# Limit_Switch_RGB_Vertical_v1_0.net
KiCad netlist of a schematic drawn in Altium Designer
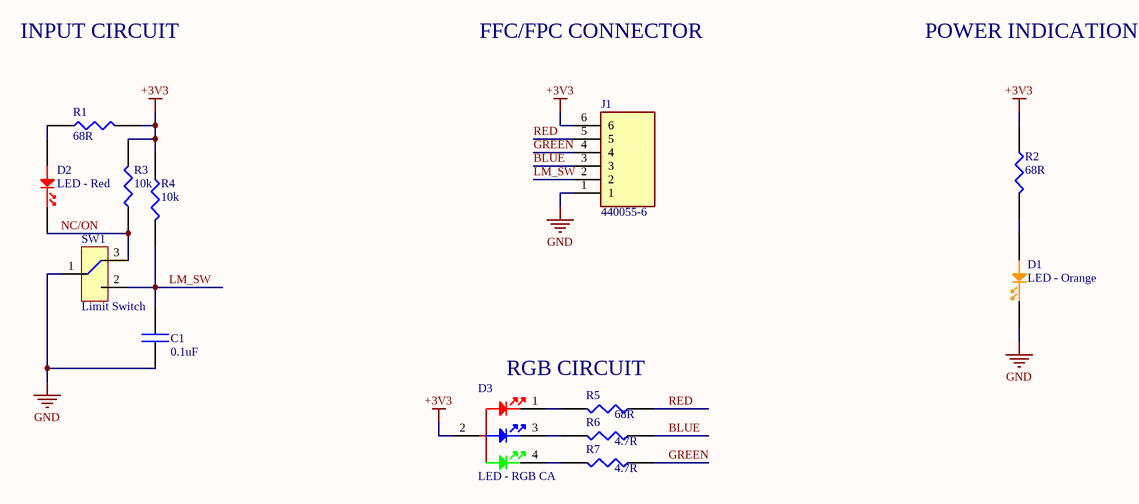
[diagram p0: Limit_Switch_RGB_Vertical_v1.0.SchDoc]

(export (version "E")
  (design (tool "Eeschema 10.0.6"))
  (components
    (comp (ref "C1")
      (value "0.1uF")
      (footprint "0.1uF 0603")
      (description "CAP CER 0.1UF 16V X7R 0603")
      (fields
        (field (name "MANUFACTURER") "KEMET")
        (field (name "MANUFACTURER PART NUMBER") "C0603C104M4RACTU")
      )
      (libsource (lib "Limit_Switch_RGB") (part "C0603C104M4RACTU"))
    )
    (comp (ref "D1")
      (value "LED - Orange")
      (footprint "LED0603-Orange")
      (description "LED ORANGE CLEAR SMD")
      (fields
        (field (name "MANUFACTURER") "Vishay Lite-On")
        (field (name "MANUFACTURER PART NUMBER") "LTST-C191KFKT")
      )
      (libsource (lib "Limit_Switch_RGB") (part "LTST-C191KFKT"))
    )
    (comp (ref "D2")
      (value "LED - Red")
      (footprint "LED RED 0603")
      (description "On a Reel of 5000, 2.4 V Red LED 1608 (0603) SMD, Lite-On LTST-C191KRKT")
      (fields
        (field (name "MANUFACTURER") "Vishay Lite-On")
        (field (name "MANUFACTURER PART NUMBER") "LTST-C191KRKT")
      )
      (libsource (lib "Limit_Switch_RGB") (part "LTST-C191KRKT"))
    )
    (comp (ref "D3")
      (value "LED - RGB CA")
      (footprint "LED RGB CA 3528")
      (description "Multicolor LED Red/Green/Blue 624nm/535nm/475nm 50mA/25mA/25mA 4-Pin SMD T/R")
      (fields
        (field (name "MANUFACTURER") "Cree")
        (field (name "MANUFACTURER PART NUMBER") "CLV1A-FKB-CK1VW1DE1BB7C3C3")
      )
      (libsource (lib "Limit_Switch_RGB") (part "CLV1A-FKB-CK1VW1DE1BB7C3C3"))
    )
    (comp (ref "J1")
      (value "440055-6")
      (footprint "TE_440055-6")
      (fields (field (name "MF") "{'manufacturer': 'TE Connectivity'}"))
      (libsource (lib "440055-6") (part "440055-6"))
    )
    (comp (ref "R1")
      (value "68R")
      (footprint "68R 0603")
      (description "CRGP 0603 68R 1%")
      (fields
        (field (name "MANUFACTURER") "TE Connectivity")
        (field (name "MANUFACTURER PART NUMBER") "CRGP0603F68R")
      )
      (libsource (lib "Limit_Switch_RGB") (part "CRGP0603F68R"))
    )
    (comp (ref "R2")
      (value "68R")
      (footprint "68R 0603")
      (description "CRGP 0603 68R 1%")
      (fields
        (field (name "MANUFACTURER") "TE Connectivity")
        (field (name "MANUFACTURER PART NUMBER") "CRGP0603F68R")
      )
      (libsource (lib "Limit_Switch_RGB") (part "CRGP0603F68R"))
    )
    (comp (ref "R3")
      (value "10k")
      (footprint "10k R0603")
      (description "RES 10.0K OHM 1/10W 1% 0603")
      (fields
        (field (name "MANUFACTURER") "TE Connectivity")
        (field (name "MANUFACTURER PART NUMBER") "CRG0603F10K/10")
      )
      (libsource (lib "Limit_Switch_RGB") (part "CRG0603F10K/10"))
    )
    (comp (ref "R4")
      (value "10k")
      (footprint "10k R0603")
      (description "RES 10.0K OHM 1/10W 1% 0603")
      (fields
        (field (name "MANUFACTURER") "TE Connectivity")
        (field (name "MANUFACTURER PART NUMBER") "CRG0603F10K/10")
      )
      (libsource (lib "Limit_Switch_RGB") (part "CRG0603F10K/10"))
    )
    (comp (ref "R5")
      (value "68R")
      (footprint "68R 0603")
      (description "CRGP 0603 68R 1%")
      (fields
        (field (name "MANUFACTURER") "TE Connectivity")
        (field (name "MANUFACTURER PART NUMBER") "CRGP0603F68R")
      )
      (libsource (lib "Limit_Switch_RGB") (part "CRGP0603F68R"))
    )
    (comp (ref "R6")
      (value "4.7R")
      (footprint "4.7R 0603")
      (fields
        (field (name "MANUFACTURER") "TE Connectivity")
        (field (name "MANUFACTURER PART NUMBER") "CRGCQ0603J4R7")
      )
      (libsource (lib "Limit_Switch_RGB") (part "CRGCQ0603J4R7"))
    )
    (comp (ref "R7")
      (value "4.7R")
      (footprint "4.7R 0603")
      (fields
        (field (name "MANUFACTURER") "TE Connectivity")
        (field (name "MANUFACTURER PART NUMBER") "CRGCQ0603J4R7")
      )
      (libsource (lib "Limit_Switch_RGB") (part "CRGCQ0603J4R7"))
    )
    (comp (ref "SW1")
      (value "Limit Switch")
      (footprint "LimitSwitch Horizontal")
      (description "Switch Snap Action N.O./N.C. SPDT Straight Lever 3A 250VAC 0.39N Thru-Hole PC Pins")
      (fields
        (field (name "MANUFACTURER") "E-Switch")
        (field (name "MANUFACTURER PART NUMBER") "SS0750301F040P1A")
      )
      (libsource (lib "Limit_Switch_RGB") (part "SS0750301F040P1A"))
    )
  )
  (nets
    (net (code "1") (name "+3V3") (class "Default")
      (node (ref "D3") (pin "2") (pinfunction "Anode_2") (pintype "passive"))
      (node (ref "J1") (pin "6") (pinfunction "6_6") (pintype "passive"))
      (node (ref "R1") (pin "2") (pinfunction "2_2") (pintype "passive"))
      (node (ref "R2") (pin "1") (pinfunction "1_1") (pintype "passive"))
      (node (ref "R3") (pin "2") (pinfunction "2_2") (pintype "passive"))
      (node (ref "R4") (pin "1") (pinfunction "1_1") (pintype "passive"))
    )
    (net (code "2") (name "/BLUE") (class "Default")
      (node (ref "J1") (pin "3") (pinfunction "3_3") (pintype "passive"))
      (node (ref "R6") (pin "1") (pinfunction "1_1") (pintype "passive"))
    )
    (net (code "3") (name "/GREEN") (class "Default")
      (node (ref "J1") (pin "4") (pinfunction "4_4") (pintype "passive"))
      (node (ref "R7") (pin "1") (pinfunction "1_1") (pintype "passive"))
    )
    (net (code "4") (name "/LM_SW") (class "Default")
      (node (ref "C1") (pin "2") (pinfunction "2_2") (pintype "passive"))
      (node (ref "J1") (pin "2") (pinfunction "2_2") (pintype "passive"))
      (node (ref "R4") (pin "2") (pinfunction "2_2") (pintype "passive"))
      (node (ref "SW1") (pin "2") (pinfunction "NO_2") (pintype "passive"))
    )
    (net (code "5") (name "/NC{slash}ON") (class "Default")
      (node (ref "D2") (pin "2") (pinfunction "Cathode_2") (pintype "passive"))
      (node (ref "R3") (pin "1") (pinfunction "1_1") (pintype "passive"))
      (node (ref "SW1") (pin "3") (pinfunction "NC_3") (pintype "passive"))
    )
    (net (code "6") (name "/RED") (class "Default")
      (node (ref "J1") (pin "5") (pinfunction "5_5") (pintype "passive"))
      (node (ref "R5") (pin "1") (pinfunction "1_1") (pintype "passive"))
    )
    (net (code "7") (name "GND") (class "Default")
      (node (ref "C1") (pin "1") (pinfunction "1_1") (pintype "passive"))
      (node (ref "D1") (pin "1") (pinfunction "Cathode_1") (pintype "passive"))
      (node (ref "J1") (pin "1") (pinfunction "1_1") (pintype "passive"))
      (node (ref "SW1") (pin "1") (pinfunction "C_1") (pintype "passive"))
    )
    (net (code "8") (name "Net-(D1-Anode)") (class "Default")
      (node (ref "D1") (pin "2") (pinfunction "Anode_2") (pintype "passive"))
      (node (ref "R2") (pin "2") (pinfunction "2_2") (pintype "passive"))
    )
    (net (code "9") (name "Net-(D2-Anode)") (class "Default")
      (node (ref "D2") (pin "1") (pinfunction "Anode_1") (pintype "passive"))
      (node (ref "R1") (pin "1") (pinfunction "1_1") (pintype "passive"))
    )
    (net (code "10") (name "Net-(D3-Blue)") (class "Default")
      (node (ref "D3") (pin "3") (pinfunction "Blue_3") (pintype "passive"))
      (node (ref "R6") (pin "2") (pinfunction "2_2") (pintype "passive"))
    )
    (net (code "11") (name "Net-(D3-Green)") (class "Default")
      (node (ref "D3") (pin "4") (pinfunction "Green_4") (pintype "passive"))
      (node (ref "R7") (pin "2") (pinfunction "2_2") (pintype "passive"))
    )
    (net (code "12") (name "Net-(D3-Red)") (class "Default")
      (node (ref "D3") (pin "1") (pinfunction "Red_1") (pintype "passive"))
      (node (ref "R5") (pin "2") (pinfunction "2_2") (pintype "passive"))
    )
  )
)
